# LoRa_Radio_915MHz_v1_0.net
KiCad netlist of a schematic drawn in EAGLE
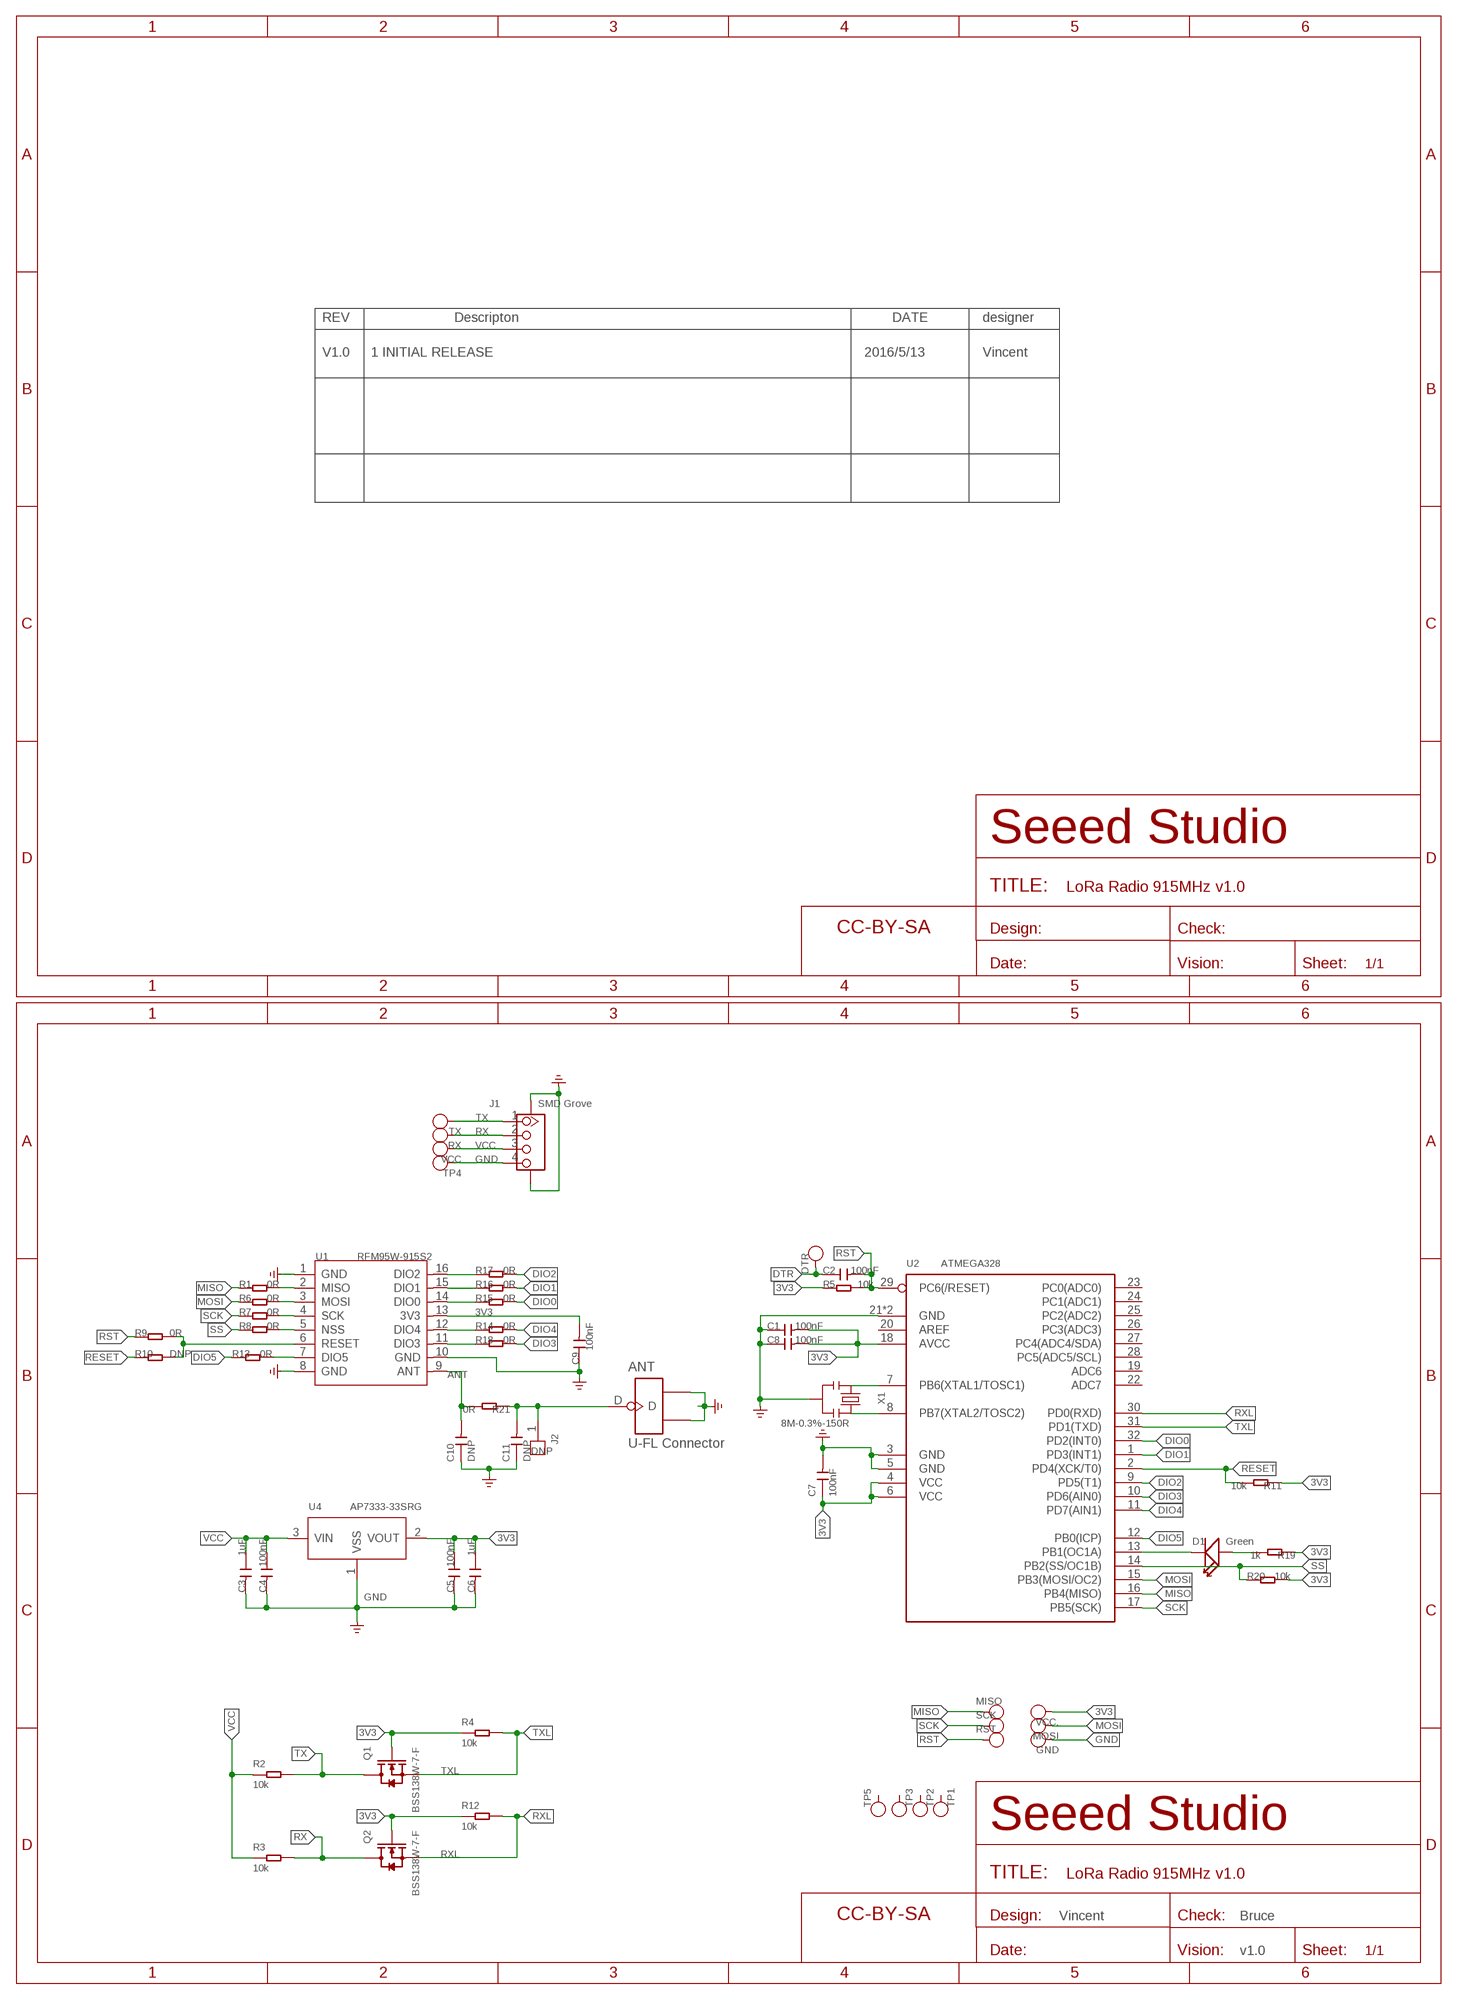
[diagram p0: schematic, sheet 1]

(export (version "E")
  (design (tool "Eeschema 10.0.6"))
  (components
    (comp (ref "ANT")
      (value "U-FL Connector")
      (footprint "eagle-import:U-FL3P-SMD-2.6X2.6X1.0MM")
      (libsource (lib "eagle-import") (part "ANTENNA-U-FL"))
    )
    (comp (ref "C1")
      (value "100nF")
      (footprint "eagle-import:C0402")
      (libsource (lib "eagle-import") (part "CAP-0402"))
    )
    (comp (ref "C2")
      (value "100nF")
      (footprint "eagle-import:C0402")
      (libsource (lib "eagle-import") (part "CAP-0402"))
    )
    (comp (ref "C3")
      (value "1uF")
      (footprint "eagle-import:C0402")
      (libsource (lib "eagle-import") (part "CAP-0402"))
    )
    (comp (ref "C4")
      (value "100nF")
      (footprint "eagle-import:C0402")
      (libsource (lib "eagle-import") (part "CAP-0402"))
    )
    (comp (ref "C5")
      (value "100nF")
      (footprint "eagle-import:C0402")
      (libsource (lib "eagle-import") (part "CAP-0402"))
    )
    (comp (ref "C6")
      (value "1uF")
      (footprint "eagle-import:C0402")
      (libsource (lib "eagle-import") (part "CAP-0402"))
    )
    (comp (ref "C7")
      (value "100nF")
      (footprint "eagle-import:C0402")
      (libsource (lib "eagle-import") (part "CAP-0402"))
    )
    (comp (ref "C8")
      (value "100nF")
      (footprint "eagle-import:C0402")
      (libsource (lib "eagle-import") (part "CAP-0402"))
    )
    (comp (ref "C9")
      (value "100nF")
      (footprint "eagle-import:C0402")
      (libsource (lib "eagle-import") (part "CAP-0402"))
    )
    (comp (ref "C10")
      (value "DNP")
      (footprint "eagle-import:C0402")
      (libsource (lib "eagle-import") (part "CAP-0402"))
    )
    (comp (ref "C11")
      (value "DNP")
      (footprint "eagle-import:C0402")
      (libsource (lib "eagle-import") (part "CAP-0402"))
    )
    (comp (ref "D1")
      (value "Green")
      (footprint "eagle-import:LED-0402")
      (libsource (lib "eagle-import") (part "LED-0402"))
    )
    (comp (ref "DTR")
      (value "TEST-POINT'4545'")
      (footprint "eagle-import:TP-D45MIL")
      (fields (field (name "PARTNO") "DNP"))
      (libsource (lib "eagle-import") (part "TEST-POINT'4545'"))
    )
    (comp (ref "FR1")
      (value "SEEEDSTUDIO-OPEN-SCH-FRAME")
      (footprint "eagle-import:SEEEDSTUDIO-PCB-FRAME")
      (libsource (lib "eagle-import") (part "SEEEDSTUDIO-OPEN-SCH-FRAME"))
    )
    (comp (ref "FR2")
      (value "SEEEDSTUDIO-OPEN-SCH-FRAME")
      (footprint "eagle-import:SEEEDSTUDIO-PCB-FRAME")
      (libsource (lib "eagle-import") (part "SEEEDSTUDIO-OPEN-SCH-FRAME"))
    )
    (comp (ref "GND")
      (value "DNP")
      (footprint "eagle-import:TP-D45MIL")
      (libsource (lib "eagle-import") (part "PAD-TEST-POINT'4545'"))
    )
    (comp (ref "J1")
      (value "SMD Grove")
      (footprint "eagle-import:HW4-SMD-2.0")
      (libsource (lib "eagle-import") (part "GROVE-CONNECTOR-SMD'DD'"))
    )
    (comp (ref "J2")
      (value "DNP")
      (footprint "eagle-import:1P-65_35MIL")
      (libsource (lib "eagle-import") (part "HEADER-1P-35"))
    )
    (comp (ref "MISO")
      (value "DNP")
      (footprint "eagle-import:TP-D45MIL")
      (libsource (lib "eagle-import") (part "PAD-TEST-POINT'4545'"))
    )
    (comp (ref "MOSI")
      (value "DNP")
      (footprint "eagle-import:TP-D45MIL")
      (libsource (lib "eagle-import") (part "PAD-TEST-POINT'4545'"))
    )
    (comp (ref "Q1")
      (value "BSS138W-7-F")
      (footprint "eagle-import:SOT-323")
      (libsource (lib "eagle-import") (part "MOSFET-N'SI1304BDL'"))
    )
    (comp (ref "Q2")
      (value "BSS138W-7-F")
      (footprint "eagle-import:SOT-323")
      (libsource (lib "eagle-import") (part "MOSFET-N'SI1304BDL'"))
    )
    (comp (ref "R1")
      (value "0R")
      (footprint "eagle-import:R0402")
      (libsource (lib "eagle-import") (part "RES-0402"))
    )
    (comp (ref "R2")
      (value "10k")
      (footprint "eagle-import:R0402")
      (libsource (lib "eagle-import") (part "RES-0402"))
    )
    (comp (ref "R3")
      (value "10k")
      (footprint "eagle-import:R0402")
      (libsource (lib "eagle-import") (part "RES-0402"))
    )
    (comp (ref "R4")
      (value "10k")
      (footprint "eagle-import:R0402")
      (libsource (lib "eagle-import") (part "RES-0402"))
    )
    (comp (ref "R5")
      (value "10k")
      (footprint "eagle-import:R0402")
      (libsource (lib "eagle-import") (part "RES-0402"))
    )
    (comp (ref "R6")
      (value "0R")
      (footprint "eagle-import:R0402")
      (libsource (lib "eagle-import") (part "RES-0402"))
    )
    (comp (ref "R7")
      (value "0R")
      (footprint "eagle-import:R0402")
      (libsource (lib "eagle-import") (part "RES-0402"))
    )
    (comp (ref "R8")
      (value "0R")
      (footprint "eagle-import:R0402")
      (libsource (lib "eagle-import") (part "RES-0402"))
    )
    (comp (ref "R9")
      (value "0R")
      (footprint "eagle-import:R0402")
      (libsource (lib "eagle-import") (part "RES-0402"))
    )
    (comp (ref "R10")
      (value "DNP")
      (footprint "eagle-import:R0402")
      (libsource (lib "eagle-import") (part "RES-0402"))
    )
    (comp (ref "R11")
      (value "10k")
      (footprint "eagle-import:R0402")
      (libsource (lib "eagle-import") (part "RES-0402"))
    )
    (comp (ref "R12")
      (value "10k")
      (footprint "eagle-import:R0402")
      (libsource (lib "eagle-import") (part "RES-0402"))
    )
    (comp (ref "R13")
      (value "0R")
      (footprint "eagle-import:R0402")
      (libsource (lib "eagle-import") (part "RES-0402"))
    )
    (comp (ref "R14")
      (value "0R")
      (footprint "eagle-import:R0402")
      (libsource (lib "eagle-import") (part "RES-0402"))
    )
    (comp (ref "R15")
      (value "0R")
      (footprint "eagle-import:R0402")
      (libsource (lib "eagle-import") (part "RES-0402"))
    )
    (comp (ref "R16")
      (value "0R")
      (footprint "eagle-import:R0402")
      (libsource (lib "eagle-import") (part "RES-0402"))
    )
    (comp (ref "R17")
      (value "0R")
      (footprint "eagle-import:R0402")
      (libsource (lib "eagle-import") (part "RES-0402"))
    )
    (comp (ref "R18")
      (value "0R")
      (footprint "eagle-import:R0402")
      (libsource (lib "eagle-import") (part "RES-0402"))
    )
    (comp (ref "R19")
      (value "1k")
      (footprint "eagle-import:R0402")
      (libsource (lib "eagle-import") (part "RES-0402"))
    )
    (comp (ref "R20")
      (value "10k")
      (footprint "eagle-import:R0402")
      (libsource (lib "eagle-import") (part "RES-0402"))
    )
    (comp (ref "R21")
      (value "0R")
      (footprint "eagle-import:R0603")
      (libsource (lib "eagle-import") (part "R-0603"))
    )
    (comp (ref "RST")
      (value "DNP")
      (footprint "eagle-import:TP-D45MIL")
      (libsource (lib "eagle-import") (part "PAD-TEST-POINT'4545'"))
    )
    (comp (ref "RX")
      (value "TEST-POINT'4545'")
      (footprint "eagle-import:TP-D45MIL")
      (fields (field (name "PARTNO") "DNP"))
      (libsource (lib "eagle-import") (part "TEST-POINT'4545'"))
    )
    (comp (ref "SCK")
      (value "DNP")
      (footprint "eagle-import:TP-D45MIL")
      (libsource (lib "eagle-import") (part "PAD-TEST-POINT'4545'"))
    )
    (comp (ref "TP1")
      (value "TEST-POINT'4545'")
      (footprint "eagle-import:TP-D45MIL")
      (fields (field (name "PARTNO") "DNP"))
      (libsource (lib "eagle-import") (part "TEST-POINT'4545'"))
    )
    (comp (ref "TP2")
      (value "TEST-POINT'4545'")
      (footprint "eagle-import:TP-D45MIL")
      (fields (field (name "PARTNO") "DNP"))
      (libsource (lib "eagle-import") (part "TEST-POINT'4545'"))
    )
    (comp (ref "TP3")
      (value "TEST-POINT'4545'")
      (footprint "eagle-import:TP-D45MIL")
      (fields (field (name "PARTNO") "DNP"))
      (libsource (lib "eagle-import") (part "TEST-POINT'4545'"))
    )
    (comp (ref "TP4")
      (value "TEST-POINT'4545'")
      (footprint "eagle-import:TP-D45MIL")
      (fields (field (name "PARTNO") "DNP"))
      (libsource (lib "eagle-import") (part "TEST-POINT'4545'"))
    )
    (comp (ref "TP5")
      (value "TEST-POINT'4545'")
      (footprint "eagle-import:TP-D45MIL")
      (fields (field (name "PARTNO") "DNP"))
      (libsource (lib "eagle-import") (part "TEST-POINT'4545'"))
    )
    (comp (ref "TX")
      (value "TEST-POINT'4545'")
      (footprint "eagle-import:TP-D45MIL")
      (fields (field (name "PARTNO") "DNP"))
      (libsource (lib "eagle-import") (part "TEST-POINT'4545'"))
    )
    (comp (ref "U1")
      (value "RFM95W-915S2")
      (footprint "eagle-import:MODEM16-2-16X16X1.8MM")
      (libsource (lib "eagle-import") (part "MOUDLE-MODEM-RFM95/96/97/98"))
    )
    (comp (ref "U2")
      (value "ATMEGA328")
      (footprint "eagle-import:QFN32G-0.5-5X5MM")
      (libsource (lib "eagle-import") (part "MCU-ATMEGA8/168/328MU"))
    )
    (comp (ref "U4")
      (value "AP7333-33SRG")
      (footprint "eagle-import:SOT-23")
      (libsource (lib "eagle-import") (part "PMIC-XC6206PMR"))
    )
    (comp (ref "VCC")
      (value "TEST-POINT'4545'")
      (footprint "eagle-import:TP-D45MIL")
      (fields (field (name "PARTNO") "DNP"))
      (libsource (lib "eagle-import") (part "TEST-POINT'4545'"))
    )
    (comp (ref "VCC.")
      (value "NC")
      (footprint "eagle-import:TP-D45MIL")
      (fields (field (name "PARTNO") "DNP"))
      (libsource (lib "eagle-import") (part "PAD-TEST-POINT'4545'"))
    )
    (comp (ref "X1")
      (value "8M-0.3%-150R")
      (footprint "eagle-import:RESONATOR3-SMD-3.6X1.3X0.8MM")
      (libsource (lib "eagle-import") (part "CRYSTAL-RESONATOR'SMD'"))
    )
  )
  (nets
    (net (code "1") (name "/ANT") (class "Default")
      (node (ref "C10") (pin "2") (pinfunction "2_2") (pintype "passive"))
      (node (ref "R21") (pin "2") (pinfunction "2_2") (pintype "passive"))
      (node (ref "U1") (pin "9") (pinfunction "ANT_9") (pintype "bidirectional"))
    )
    (net (code "2") (name "3V3") (class "Default")
      (node (ref "C1") (pin "2") (pinfunction "2_2") (pintype "passive"))
      (node (ref "C5") (pin "1") (pinfunction "1_1") (pintype "passive"))
      (node (ref "C6") (pin "1") (pinfunction "1_1") (pintype "passive"))
      (node (ref "C7") (pin "1") (pinfunction "1_1") (pintype "passive"))
      (node (ref "C8") (pin "2") (pinfunction "2_2") (pintype "passive"))
      (node (ref "C9") (pin "2") (pinfunction "2_2") (pintype "passive"))
      (node (ref "Q1") (pin "1") (pinfunction "G_1") (pintype "passive"))
      (node (ref "Q2") (pin "1") (pinfunction "G_1") (pintype "passive"))
      (node (ref "R11") (pin "2") (pinfunction "2_2") (pintype "passive"))
      (node (ref "R12") (pin "1") (pinfunction "1_1") (pintype "passive"))
      (node (ref "R19") (pin "2") (pinfunction "2_2") (pintype "passive"))
      (node (ref "R20") (pin "2") (pinfunction "2_2") (pintype "passive"))
      (node (ref "R4") (pin "1") (pinfunction "1_1") (pintype "passive"))
      (node (ref "R5") (pin "2") (pinfunction "2_2") (pintype "passive"))
      (node (ref "U1") (pin "13") (pinfunction "3V3_13") (pintype "bidirectional"))
      (node (ref "U2") (pin "18") (pinfunction "AVCC_18") (pintype "bidirectional"))
      (node (ref "U2") (pin "4") (pinfunction "VCC_4") (pintype "bidirectional"))
      (node (ref "U2") (pin "6") (pinfunction "VCC_6") (pintype "bidirectional"))
      (node (ref "U4") (pin "2") (pinfunction "VOUT_2") (pintype "bidirectional"))
      (node (ref "VCC.") (pin "T") (pinfunction "T_T") (pintype "bidirectional"))
    )
    (net (code "3") (name "DIO0") (class "Default")
      (node (ref "R15") (pin "2") (pinfunction "2_2") (pintype "passive"))
      (node (ref "U2") (pin "32") (pinfunction "PD2(INT0)_32") (pintype "bidirectional"))
    )
    (net (code "4") (name "DIO1") (class "Default")
      (node (ref "R16") (pin "2") (pinfunction "2_2") (pintype "passive"))
      (node (ref "U2") (pin "1") (pinfunction "PD3(INT1)_1") (pintype "bidirectional"))
    )
    (net (code "5") (name "DIO2") (class "Default")
      (node (ref "R17") (pin "2") (pinfunction "2_2") (pintype "passive"))
      (node (ref "U2") (pin "9") (pinfunction "PD5(T1)_9") (pintype "bidirectional"))
    )
    (net (code "6") (name "DIO3") (class "Default")
      (node (ref "R18") (pin "2") (pinfunction "2_2") (pintype "passive"))
      (node (ref "U2") (pin "10") (pinfunction "PD6(AIN0)_10") (pintype "bidirectional"))
    )
    (net (code "7") (name "DIO4") (class "Default")
      (node (ref "R14") (pin "2") (pinfunction "2_2") (pintype "passive"))
      (node (ref "U2") (pin "11") (pinfunction "PD7(AIN1)_11") (pintype "bidirectional"))
    )
    (net (code "8") (name "DIO5") (class "Default")
      (node (ref "R13") (pin "1") (pinfunction "1_1") (pintype "passive"))
      (node (ref "U2") (pin "12") (pinfunction "PB0(ICP)_12") (pintype "bidirectional"))
    )
    (net (code "9") (name "DTR") (class "Default")
      (node (ref "C2") (pin "1") (pinfunction "1_1") (pintype "passive"))
      (node (ref "DTR") (pin "T") (pinfunction "T_T") (pintype "bidirectional"))
    )
    (net (code "10") (name "GND") (class "Default")
      (node (ref "ANT") (pin "GND1") (pinfunction "GND1_GND1") (pintype "bidirectional"))
      (node (ref "ANT") (pin "GND2") (pinfunction "GND2_GND2") (pintype "bidirectional"))
      (node (ref "C1") (pin "1") (pinfunction "1_1") (pintype "passive"))
      (node (ref "C10") (pin "1") (pinfunction "1_1") (pintype "passive"))
      (node (ref "C11") (pin "1") (pinfunction "1_1") (pintype "passive"))
      (node (ref "C3") (pin "2") (pinfunction "2_2") (pintype "passive"))
      (node (ref "C4") (pin "2") (pinfunction "2_2") (pintype "passive"))
      (node (ref "C5") (pin "2") (pinfunction "2_2") (pintype "passive"))
      (node (ref "C6") (pin "2") (pinfunction "2_2") (pintype "passive"))
      (node (ref "C7") (pin "2") (pinfunction "2_2") (pintype "passive"))
      (node (ref "C8") (pin "1") (pinfunction "1_1") (pintype "passive"))
      (node (ref "C9") (pin "1") (pinfunction "1_1") (pintype "passive"))
      (node (ref "GND") (pin "T") (pinfunction "T_T") (pintype "bidirectional"))
      (node (ref "J1") (pin "4") (pinfunction "4_4") (pintype "bidirectional"))
      (node (ref "J1") (pin "SS1") (pinfunction "SS1_SS1") (pintype "bidirectional"))
      (node (ref "J1") (pin "SS2") (pinfunction "SS2_SS2") (pintype "bidirectional"))
      (node (ref "TP4") (pin "T") (pinfunction "T_T") (pintype "bidirectional"))
      (node (ref "U1") (pin "1") (pinfunction "GND_1") (pintype "bidirectional"))
      (node (ref "U1") (pin "10") (pinfunction "GND_10") (pintype "bidirectional"))
      (node (ref "U1") (pin "8") (pinfunction "GND_8") (pintype "bidirectional"))
      (node (ref "U2") (pin "21") (pinfunction "GND_21") (pintype "bidirectional"))
      (node (ref "U2") (pin "3") (pinfunction "GND_3") (pintype "bidirectional"))
      (node (ref "U2") (pin "33") (pinfunction "GND_33") (pintype "bidirectional"))
      (node (ref "U2") (pin "5") (pinfunction "GND_5") (pintype "bidirectional"))
      (node (ref "U4") (pin "1") (pinfunction "VSS_1") (pintype "bidirectional"))
      (node (ref "X1") (pin "2") (pinfunction "2_2") (pintype "passive"))
    )
    (net (code "11") (name "MISO") (class "Default")
      (node (ref "MISO") (pin "T") (pinfunction "T_T") (pintype "bidirectional"))
      (node (ref "R1") (pin "1") (pinfunction "1_1") (pintype "passive"))
      (node (ref "U2") (pin "16") (pinfunction "PB4(MISO)_16") (pintype "bidirectional"))
    )
    (net (code "12") (name "MOSI") (class "Default")
      (node (ref "MOSI") (pin "T") (pinfunction "T_T") (pintype "bidirectional"))
      (node (ref "R6") (pin "1") (pinfunction "1_1") (pintype "passive"))
      (node (ref "U2") (pin "15") (pinfunction "PB3(MOSI/OC2)_15") (pintype "bidirectional"))
    )
    (net (code "13") (name "Net-(ANT-PadD)") (class "Default")
      (node (ref "ANT") (pin "D") (pinfunction "D_D") (pintype "bidirectional"))
      (node (ref "C11") (pin "2") (pinfunction "2_2") (pintype "passive"))
      (node (ref "J2") (pin "1") (pinfunction "1_1") (pintype "bidirectional"))
      (node (ref "R21") (pin "1") (pinfunction "1_1") (pintype "passive"))
    )
    (net (code "14") (name "Net-(D1-Pad+)") (class "Default")
      (node (ref "D1") (pin "+") (pinfunction "+_+") (pintype "passive"))
      (node (ref "R19") (pin "1") (pinfunction "1_1") (pintype "passive"))
    )
    (net (code "15") (name "Net-(U1-DIO0)") (class "Default")
      (node (ref "R15") (pin "1") (pinfunction "1_1") (pintype "passive"))
      (node (ref "U1") (pin "14") (pinfunction "DIO0_14") (pintype "bidirectional"))
    )
    (net (code "16") (name "Net-(U1-DIO1)") (class "Default")
      (node (ref "R16") (pin "1") (pinfunction "1_1") (pintype "passive"))
      (node (ref "U1") (pin "15") (pinfunction "DIO1_15") (pintype "bidirectional"))
    )
    (net (code "17") (name "Net-(U1-DIO2)") (class "Default")
      (node (ref "R17") (pin "1") (pinfunction "1_1") (pintype "passive"))
      (node (ref "U1") (pin "16") (pinfunction "DIO2_16") (pintype "bidirectional"))
    )
    (net (code "18") (name "Net-(U1-DIO3)") (class "Default")
      (node (ref "R18") (pin "1") (pinfunction "1_1") (pintype "passive"))
      (node (ref "U1") (pin "11") (pinfunction "DIO3_11") (pintype "bidirectional"))
    )
    (net (code "19") (name "Net-(U1-DIO4)") (class "Default")
      (node (ref "R14") (pin "1") (pinfunction "1_1") (pintype "passive"))
      (node (ref "U1") (pin "12") (pinfunction "DIO4_12") (pintype "bidirectional"))
    )
    (net (code "20") (name "Net-(U1-DIO5)") (class "Default")
      (node (ref "R13") (pin "2") (pinfunction "2_2") (pintype "passive"))
      (node (ref "U1") (pin "7") (pinfunction "DIO5_7") (pintype "bidirectional"))
    )
    (net (code "21") (name "Net-(U1-MISO)") (class "Default")
      (node (ref "R1") (pin "2") (pinfunction "2_2") (pintype "passive"))
      (node (ref "U1") (pin "2") (pinfunction "MISO_2") (pintype "bidirectional"))
    )
    (net (code "22") (name "Net-(U1-MOSI)") (class "Default")
      (node (ref "R6") (pin "2") (pinfunction "2_2") (pintype "passive"))
      (node (ref "U1") (pin "3") (pinfunction "MOSI_3") (pintype "bidirectional"))
    )
    (net (code "23") (name "Net-(U1-NSS)") (class "Default")
      (node (ref "R8") (pin "2") (pinfunction "2_2") (pintype "passive"))
      (node (ref "U1") (pin "5") (pinfunction "NSS_5") (pintype "bidirectional"))
    )
    (net (code "24") (name "Net-(U1-RESET)") (class "Default")
      (node (ref "R10") (pin "1") (pinfunction "1_1") (pintype "passive"))
      (node (ref "R9") (pin "1") (pinfunction "1_1") (pintype "passive"))
      (node (ref "U1") (pin "6") (pinfunction "RESET_6") (pintype "bidirectional"))
    )
    (net (code "25") (name "Net-(U1-SCK)") (class "Default")
      (node (ref "R7") (pin "2") (pinfunction "2_2") (pintype "passive"))
      (node (ref "U1") (pin "4") (pinfunction "SCK_4") (pintype "bidirectional"))
    )
    (net (code "26") (name "Net-(U2-PB1(OC1A))") (class "Default")
      (node (ref "D1") (pin "-") (pinfunction "-_-") (pintype "passive"))
      (node (ref "U2") (pin "13") (pinfunction "PB1(OC1A)_13") (pintype "bidirectional"))
    )
    (net (code "27") (name "Net-(U2-PB6(XTAL1{slash}TOSC1))") (class "Default")
      (node (ref "U2") (pin "7") (pinfunction "PB6(XTAL1/TOSC1)_7") (pintype "bidirectional"))
      (node (ref "X1") (pin "1") (pinfunction "1_1") (pintype "passive"))
    )
    (net (code "28") (name "Net-(U2-PB7(XTAL2{slash}TOSC2))") (class "Default")
      (node (ref "U2") (pin "8") (pinfunction "PB7(XTAL2/TOSC2)_8") (pintype "bidirectional"))
      (node (ref "X1") (pin "3") (pinfunction "3_3") (pintype "passive"))
    )
    (net (code "29") (name "RESET") (class "Default")
      (node (ref "R10") (pin "2") (pinfunction "2_2") (pintype "passive"))
      (node (ref "R11") (pin "1") (pinfunction "1_1") (pintype "passive"))
      (node (ref "U2") (pin "2") (pinfunction "PD4(XCK/T0)_2") (pintype "bidirectional"))
    )
    (net (code "30") (name "RST") (class "Default")
      (node (ref "C2") (pin "2") (pinfunction "2_2") (pintype "passive"))
      (node (ref "R5") (pin "1") (pinfunction "1_1") (pintype "passive"))
      (node (ref "R9") (pin "2") (pinfunction "2_2") (pintype "passive"))
      (node (ref "RST") (pin "T") (pinfunction "T_T") (pintype "bidirectional"))
      (node (ref "U2") (pin "29") (pinfunction "PC6(/RESET)_29") (pintype "bidirectional"))
    )
    (net (code "31") (name "RX") (class "Default")
      (node (ref "J1") (pin "2") (pinfunction "2_2") (pintype "bidirectional"))
      (node (ref "Q2") (pin "3") (pinfunction "D_3") (pintype "passive"))
      (node (ref "R3") (pin "2") (pinfunction "2_2") (pintype "passive"))
      (node (ref "RX") (pin "T") (pinfunction "T_T") (pintype "bidirectional"))
    )
    (net (code "32") (name "RXL") (class "Default")
      (node (ref "Q2") (pin "2") (pinfunction "S_2") (pintype "passive"))
      (node (ref "R12") (pin "2") (pinfunction "2_2") (pintype "passive"))
      (node (ref "U2") (pin "30") (pinfunction "PD0(RXD)_30") (pintype "bidirectional"))
    )
    (net (code "33") (name "SCK") (class "Default")
      (node (ref "R7") (pin "1") (pinfunction "1_1") (pintype "passive"))
      (node (ref "SCK") (pin "T") (pinfunction "T_T") (pintype "bidirectional"))
      (node (ref "U2") (pin "17") (pinfunction "PB5(SCK)_17") (pintype "bidirectional"))
    )
    (net (code "34") (name "SS") (class "Default")
      (node (ref "R20") (pin "1") (pinfunction "1_1") (pintype "passive"))
      (node (ref "R8") (pin "1") (pinfunction "1_1") (pintype "passive"))
      (node (ref "U2") (pin "14") (pinfunction "PB2(SS/OC1B)_14") (pintype "bidirectional"))
    )
    (net (code "35") (name "TX") (class "Default")
      (node (ref "J1") (pin "1") (pinfunction "1_1") (pintype "bidirectional"))
      (node (ref "Q1") (pin "3") (pinfunction "D_3") (pintype "passive"))
      (node (ref "R2") (pin "2") (pinfunction "2_2") (pintype "passive"))
      (node (ref "TX") (pin "T") (pinfunction "T_T") (pintype "bidirectional"))
    )
    (net (code "36") (name "TXL") (class "Default")
      (node (ref "Q1") (pin "2") (pinfunction "S_2") (pintype "passive"))
      (node (ref "R4") (pin "2") (pinfunction "2_2") (pintype "passive"))
      (node (ref "U2") (pin "31") (pinfunction "PD1(TXD)_31") (pintype "bidirectional"))
    )
    (net (code "37") (name "VCC") (class "Default")
      (node (ref "C3") (pin "1") (pinfunction "1_1") (pintype "passive"))
      (node (ref "C4") (pin "1") (pinfunction "1_1") (pintype "passive"))
      (node (ref "J1") (pin "3") (pinfunction "3_3") (pintype "bidirectional"))
      (node (ref "R2") (pin "1") (pinfunction "1_1") (pintype "passive"))
      (node (ref "R3") (pin "1") (pinfunction "1_1") (pintype "passive"))
      (node (ref "U4") (pin "3") (pinfunction "VIN_3") (pintype "bidirectional"))
      (node (ref "VCC") (pin "T") (pinfunction "T_T") (pintype "bidirectional"))
    )
    (net (code "38") (name "unconnected-(TP1-PadT)") (class "Default")
      (node (ref "TP1") (pin "T") (pinfunction "T_T") (pintype "bidirectional"))
    )
    (net (code "39") (name "unconnected-(TP2-PadT)") (class "Default")
      (node (ref "TP2") (pin "T") (pinfunction "T_T") (pintype "bidirectional"))
    )
    (net (code "40") (name "unconnected-(TP3-PadT)") (class "Default")
      (node (ref "TP3") (pin "T") (pinfunction "T_T") (pintype "bidirectional"))
    )
    (net (code "41") (name "unconnected-(TP5-PadT)") (class "Default")
      (node (ref "TP5") (pin "T") (pinfunction "T_T") (pintype "bidirectional"))
    )
    (net (code "42") (name "unconnected-(U2-ADC6-Pad19)") (class "Default")
      (node (ref "U2") (pin "19") (pinfunction "ADC6_19") (pintype "bidirectional"))
    )
    (net (code "43") (name "unconnected-(U2-ADC7-Pad22)") (class "Default")
      (node (ref "U2") (pin "22") (pinfunction "ADC7_22") (pintype "bidirectional"))
    )
    (net (code "44") (name "unconnected-(U2-AREF-Pad20)") (class "Default")
      (node (ref "U2") (pin "20") (pinfunction "AREF_20") (pintype "bidirectional"))
    )
    (net (code "45") (name "unconnected-(U2-PC0(ADC0)-Pad23)") (class "Default")
      (node (ref "U2") (pin "23") (pinfunction "PC0(ADC0)_23") (pintype "bidirectional"))
    )
    (net (code "46") (name "unconnected-(U2-PC1(ADC1)-Pad24)") (class "Default")
      (node (ref "U2") (pin "24") (pinfunction "PC1(ADC1)_24") (pintype "bidirectional"))
    )
    (net (code "47") (name "unconnected-(U2-PC2(ADC2)-Pad25)") (class "Default")
      (node (ref "U2") (pin "25") (pinfunction "PC2(ADC2)_25") (pintype "bidirectional"))
    )
    (net (code "48") (name "unconnected-(U2-PC3(ADC3)-Pad26)") (class "Default")
      (node (ref "U2") (pin "26") (pinfunction "PC3(ADC3)_26") (pintype "bidirectional"))
    )
    (net (code "49") (name "unconnected-(U2-PC4(ADC4{slash}SDA)-Pad27)") (class "Default")
      (node (ref "U2") (pin "27") (pinfunction "PC4(ADC4/SDA)_27") (pintype "bidirectional"))
    )
    (net (code "50") (name "unconnected-(U2-PC5(ADC5{slash}SCL)-Pad28)") (class "Default")
      (node (ref "U2") (pin "28") (pinfunction "PC5(ADC5/SCL)_28") (pintype "bidirectional"))
    )
  )
)
